# Mikroi_lemci.net
KiCad netlist of a schematic drawn in Altium Designer
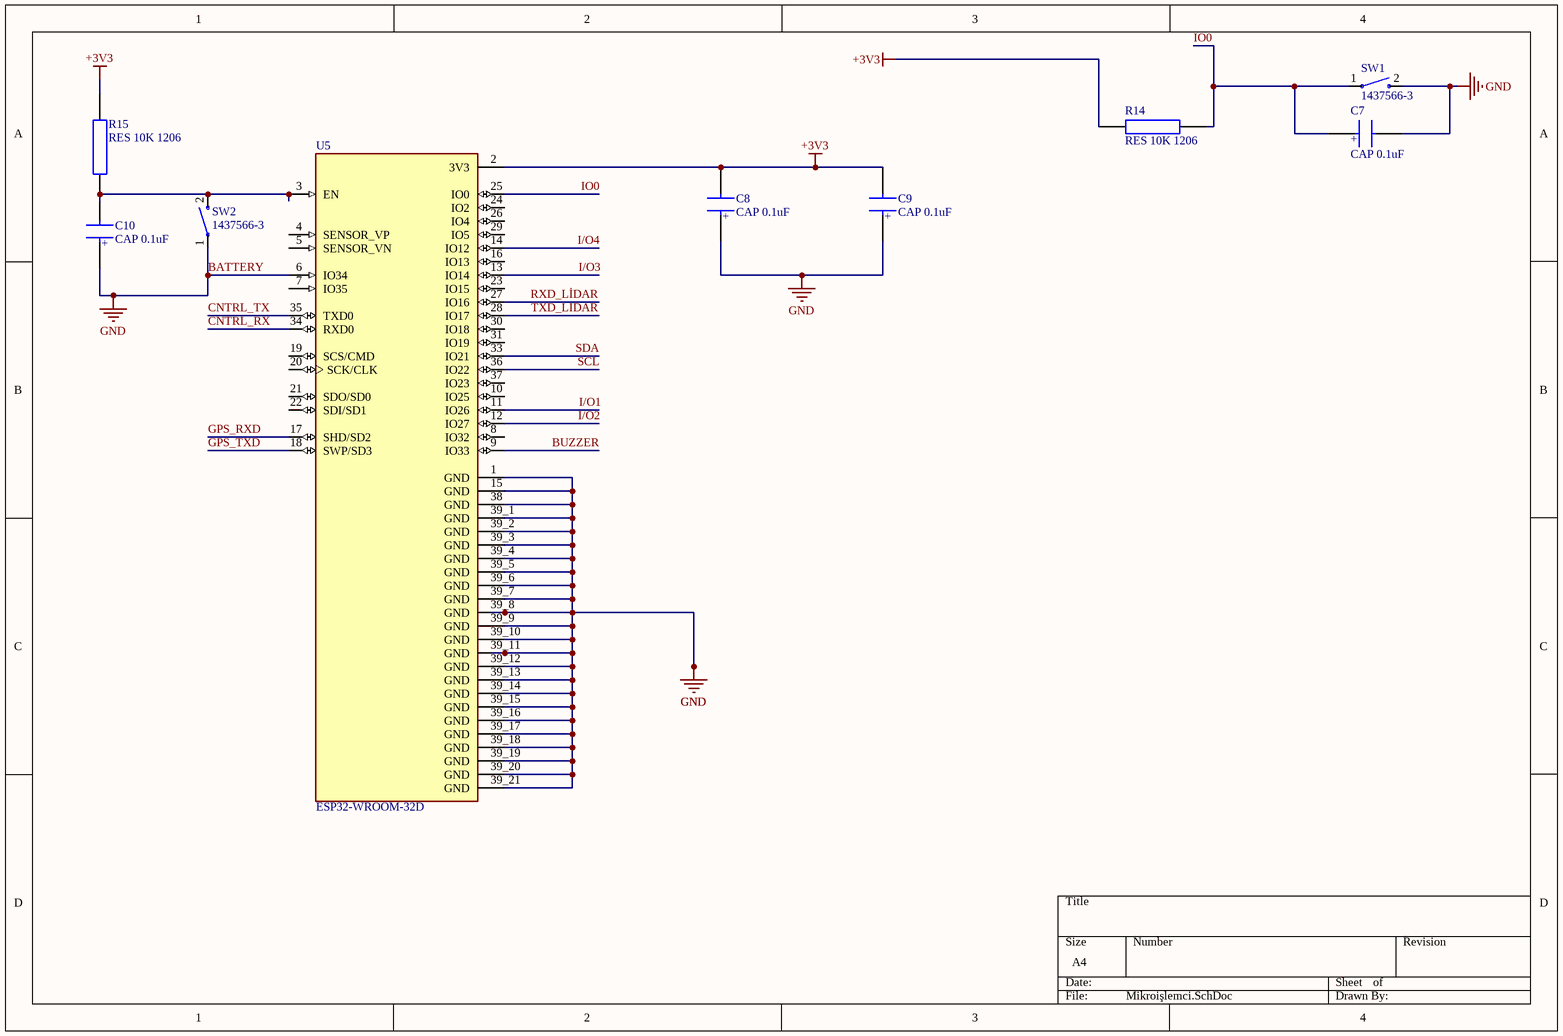
[diagram p0: Mikroişlemci.SchDoc]

(export (version "E")
  (design (tool "Eeschema 10.0.6"))
  (components
    (comp (ref "C7")
      (value "CAP 0.1uF")
      (footprint "CAP_805")
      (description "0805 smd")
      (libsource (lib "Udemy_Schlib1") (part "CAP 1uF"))
    )
    (comp (ref "C8")
      (value "CAP 0.1uF")
      (footprint "CAP_805")
      (description "0805 smd")
      (libsource (lib "Udemy_Schlib1") (part "CAP 1uF"))
    )
    (comp (ref "C9")
      (value "CAP 0.1uF")
      (footprint "CAP_805")
      (description "0805 smd")
      (libsource (lib "Udemy_Schlib1") (part "CAP 1uF"))
    )
    (comp (ref "C10")
      (value "CAP 0.1uF")
      (footprint "CAP_805")
      (description "0805 smd")
      (libsource (lib "Udemy_Schlib1") (part "CAP 1uF"))
    )
    (comp (ref "R14")
      (value "RES 10K 1206")
      (footprint "RES_1206")
      (libsource (lib "Udemy_Schlib1") (part "RES 10K 1206"))
    )
    (comp (ref "R15")
      (value "RES 10K 1206")
      (footprint "RES_1206")
      (libsource (lib "Udemy_Schlib1") (part "RES 10K 1206"))
    )
    (comp (ref "SW1")
      (value "1437566-3")
      (footprint "SW_1437566-3")
      (description "Switch Tactile OFF (ON) SPST Rectangular Button Gull Wing 0.05A 12VDC SMD Loose Piece")
      (libsource (lib "Schlib") (part "1437566-3"))
    )
    (comp (ref "SW2")
      (value "1437566-3")
      (footprint "SW_1437566-3")
      (description "Switch Tactile OFF (ON) SPST Rectangular Button Gull Wing 0.05A 12VDC SMD Loose Piece")
      (libsource (lib "Schlib") (part "1437566-3"))
    )
    (comp (ref "U5")
      (value "ESP32-WROOM-32D")
      (footprint "MODULE_ESP32-WROOM-32D")
      (fields (field (name "MF") "Espressif Systems"))
      (libsource (lib "Schlib") (part "ESP32-WROOM-32D"))
    )
  )
  (nets
    (net (code "1") (name "+3V3") (class "Default")
      (node (ref "C8") (pin "2") (pinfunction "2_2") (pintype "passive"))
      (node (ref "C9") (pin "2") (pinfunction "2_2") (pintype "passive"))
      (node (ref "R14") (pin "2") (pintype "passive"))
      (node (ref "R15") (pin "2") (pintype "passive"))
      (node (ref "U5") (pin "2") (pinfunction "3V3_2") (pintype "power_in"))
    )
    (net (code "2") (name "/BUZZER") (class "Default")
      (node (ref "U5") (pin "9") (pinfunction "IO33_9") (pintype "bidirectional"))
    )
    (net (code "3") (name "/CNTRL_RX") (class "Default")
      (node (ref "U5") (pin "34") (pinfunction "RXD0_34") (pintype "bidirectional"))
    )
    (net (code "4") (name "/CNTRL_TX") (class "Default")
      (node (ref "U5") (pin "35") (pinfunction "TXD0_35") (pintype "bidirectional"))
    )
    (net (code "5") (name "/GPS_RXD") (class "Default")
      (node (ref "U5") (pin "17") (pinfunction "SHD/SD2_17") (pintype "bidirectional"))
    )
    (net (code "6") (name "/GPS_TXD") (class "Default")
      (node (ref "U5") (pin "18") (pinfunction "SWP/SD3_18") (pintype "bidirectional"))
    )
    (net (code "7") (name "/IO0") (class "Default")
      (node (ref "C7") (pin "1") (pinfunction "1_1") (pintype "passive"))
      (node (ref "R14") (pin "1") (pintype "passive"))
      (node (ref "SW1") (pin "1") (pinfunction "1_1") (pintype "passive"))
      (node (ref "U5") (pin "25") (pinfunction "IO0_25") (pintype "bidirectional"))
    )
    (net (code "8") (name "/I{slash}O1") (class "Default")
      (node (ref "U5") (pin "11") (pinfunction "IO26_11") (pintype "bidirectional"))
    )
    (net (code "9") (name "/I{slash}O2") (class "Default")
      (node (ref "U5") (pin "12") (pinfunction "IO27_12") (pintype "bidirectional"))
    )
    (net (code "10") (name "/I{slash}O3") (class "Default")
      (node (ref "U5") (pin "13") (pinfunction "IO14_13") (pintype "bidirectional"))
    )
    (net (code "11") (name "/I{slash}O4") (class "Default")
      (node (ref "U5") (pin "14") (pinfunction "IO12_14") (pintype "bidirectional"))
    )
    (net (code "12") (name "/RXD_LİDAR") (class "Default")
      (node (ref "U5") (pin "27") (pinfunction "IO16_27") (pintype "bidirectional"))
    )
    (net (code "13") (name "/SCL") (class "Default")
      (node (ref "U5") (pin "36") (pinfunction "IO22_36") (pintype "bidirectional"))
    )
    (net (code "14") (name "/SDA") (class "Default")
      (node (ref "U5") (pin "33") (pinfunction "IO21_33") (pintype "bidirectional"))
    )
    (net (code "15") (name "/TXD_LİDAR") (class "Default")
      (node (ref "U5") (pin "28") (pinfunction "IO17_28") (pintype "bidirectional"))
    )
    (net (code "16") (name "GND") (class "Default")
      (node (ref "C10") (pin "1") (pinfunction "1_1") (pintype "passive"))
      (node (ref "C7") (pin "2") (pinfunction "2_2") (pintype "passive"))
      (node (ref "C8") (pin "1") (pinfunction "1_1") (pintype "passive"))
      (node (ref "C9") (pin "1") (pinfunction "1_1") (pintype "passive"))
      (node (ref "SW1") (pin "2") (pinfunction "2_2") (pintype "passive"))
      (node (ref "SW2") (pin "1") (pinfunction "1_1") (pintype "passive"))
      (node (ref "U5") (pin "1") (pinfunction "GND_1") (pintype "power_in"))
      (node (ref "U5") (pin "15") (pinfunction "GND_15") (pintype "power_in"))
      (node (ref "U5") (pin "38") (pinfunction "GND_38") (pintype "power_in"))
      (node (ref "U5") (pin "39_1") (pinfunction "GND_39_1") (pintype "power_in"))
      (node (ref "U5") (pin "39_10") (pinfunction "GND_39_10") (pintype "power_in"))
      (node (ref "U5") (pin "39_11") (pinfunction "GND_39_11") (pintype "power_in"))
      (node (ref "U5") (pin "39_12") (pinfunction "GND_39_12") (pintype "power_in"))
      (node (ref "U5") (pin "39_13") (pinfunction "GND_39_13") (pintype "power_in"))
      (node (ref "U5") (pin "39_14") (pinfunction "GND_39_14") (pintype "power_in"))
      (node (ref "U5") (pin "39_15") (pinfunction "GND_39_15") (pintype "power_in"))
      (node (ref "U5") (pin "39_16") (pinfunction "GND_39_16") (pintype "power_in"))
      (node (ref "U5") (pin "39_17") (pinfunction "GND_39_17") (pintype "power_in"))
      (node (ref "U5") (pin "39_18") (pinfunction "GND_39_18") (pintype "power_in"))
      (node (ref "U5") (pin "39_19") (pinfunction "GND_39_19") (pintype "power_in"))
      (node (ref "U5") (pin "39_2") (pinfunction "GND_39_2") (pintype "power_in"))
      (node (ref "U5") (pin "39_20") (pinfunction "GND_39_20") (pintype "power_in"))
      (node (ref "U5") (pin "39_21") (pinfunction "GND_39_21") (pintype "power_in"))
      (node (ref "U5") (pin "39_3") (pinfunction "GND_39_3") (pintype "power_in"))
      (node (ref "U5") (pin "39_4") (pinfunction "GND_39_4") (pintype "power_in"))
      (node (ref "U5") (pin "39_5") (pinfunction "GND_39_5") (pintype "power_in"))
      (node (ref "U5") (pin "39_6") (pinfunction "GND_39_6") (pintype "power_in"))
      (node (ref "U5") (pin "39_7") (pinfunction "GND_39_7") (pintype "power_in"))
      (node (ref "U5") (pin "39_8") (pinfunction "GND_39_8") (pintype "power_in"))
      (node (ref "U5") (pin "39_9") (pinfunction "GND_39_9") (pintype "power_in"))
      (node (ref "U5") (pin "6") (pinfunction "IO34_6") (pintype "input"))
    )
    (net (code "17") (name "Net-(U5-EN)") (class "Default")
      (node (ref "C10") (pin "2") (pinfunction "2_2") (pintype "passive"))
      (node (ref "R15") (pin "1") (pintype "passive"))
      (node (ref "SW2") (pin "2") (pinfunction "2_2") (pintype "passive"))
      (node (ref "U5") (pin "3") (pinfunction "EN_3") (pintype "input"))
    )
    (net (code "18") (name "unconnected-(U5-IO2-Pad24)") (class "Default")
      (node (ref "U5") (pin "24") (pinfunction "IO2_24") (pintype "bidirectional"))
    )
    (net (code "19") (name "unconnected-(U5-IO4-Pad26)") (class "Default")
      (node (ref "U5") (pin "26") (pinfunction "IO4_26") (pintype "bidirectional"))
    )
    (net (code "20") (name "unconnected-(U5-IO5-Pad29)") (class "Default")
      (node (ref "U5") (pin "29") (pinfunction "IO5_29") (pintype "bidirectional"))
    )
    (net (code "21") (name "unconnected-(U5-IO13-Pad16)") (class "Default")
      (node (ref "U5") (pin "16") (pinfunction "IO13_16") (pintype "bidirectional"))
    )
    (net (code "22") (name "unconnected-(U5-IO15-Pad23)") (class "Default")
      (node (ref "U5") (pin "23") (pinfunction "IO15_23") (pintype "bidirectional"))
    )
    (net (code "23") (name "unconnected-(U5-IO18-Pad30)") (class "Default")
      (node (ref "U5") (pin "30") (pinfunction "IO18_30") (pintype "bidirectional"))
    )
    (net (code "24") (name "unconnected-(U5-IO19-Pad31)") (class "Default")
      (node (ref "U5") (pin "31") (pinfunction "IO19_31") (pintype "bidirectional"))
    )
    (net (code "25") (name "unconnected-(U5-IO23-Pad37)") (class "Default")
      (node (ref "U5") (pin "37") (pinfunction "IO23_37") (pintype "bidirectional"))
    )
    (net (code "26") (name "unconnected-(U5-IO25-Pad10)") (class "Default")
      (node (ref "U5") (pin "10") (pinfunction "IO25_10") (pintype "bidirectional"))
    )
    (net (code "27") (name "unconnected-(U5-IO32-Pad8)") (class "Default")
      (node (ref "U5") (pin "8") (pinfunction "IO32_8") (pintype "bidirectional"))
    )
    (net (code "28") (name "unconnected-(U5-IO35-Pad7)") (class "Default")
      (node (ref "U5") (pin "7") (pinfunction "IO35_7") (pintype "input"))
    )
    (net (code "29") (name "unconnected-(U5-SCK{slash}CLK-Pad20)") (class "Default")
      (node (ref "U5") (pin "20") (pinfunction "SCK/CLK_20") (pintype "bidirectional"))
    )
    (net (code "30") (name "unconnected-(U5-SCS{slash}CMD-Pad19)") (class "Default")
      (node (ref "U5") (pin "19") (pinfunction "SCS/CMD_19") (pintype "bidirectional"))
    )
    (net (code "31") (name "unconnected-(U5-SDI{slash}SD1-Pad22)") (class "Default")
      (node (ref "U5") (pin "22") (pinfunction "SDI/SD1_22") (pintype "bidirectional"))
    )
    (net (code "32") (name "unconnected-(U5-SDO{slash}SD0-Pad21)") (class "Default")
      (node (ref "U5") (pin "21") (pinfunction "SDO/SD0_21") (pintype "bidirectional"))
    )
    (net (code "33") (name "unconnected-(U5-SENSOR_VN-Pad5)") (class "Default")
      (node (ref "U5") (pin "5") (pinfunction "SENSOR_VN_5") (pintype "input"))
    )
    (net (code "34") (name "unconnected-(U5-SENSOR_VP-Pad4)") (class "Default")
      (node (ref "U5") (pin "4") (pinfunction "SENSOR_VP_4") (pintype "input"))
    )
  )
)
